# MCU.net
KiCad netlist of a schematic drawn in Altium Designer
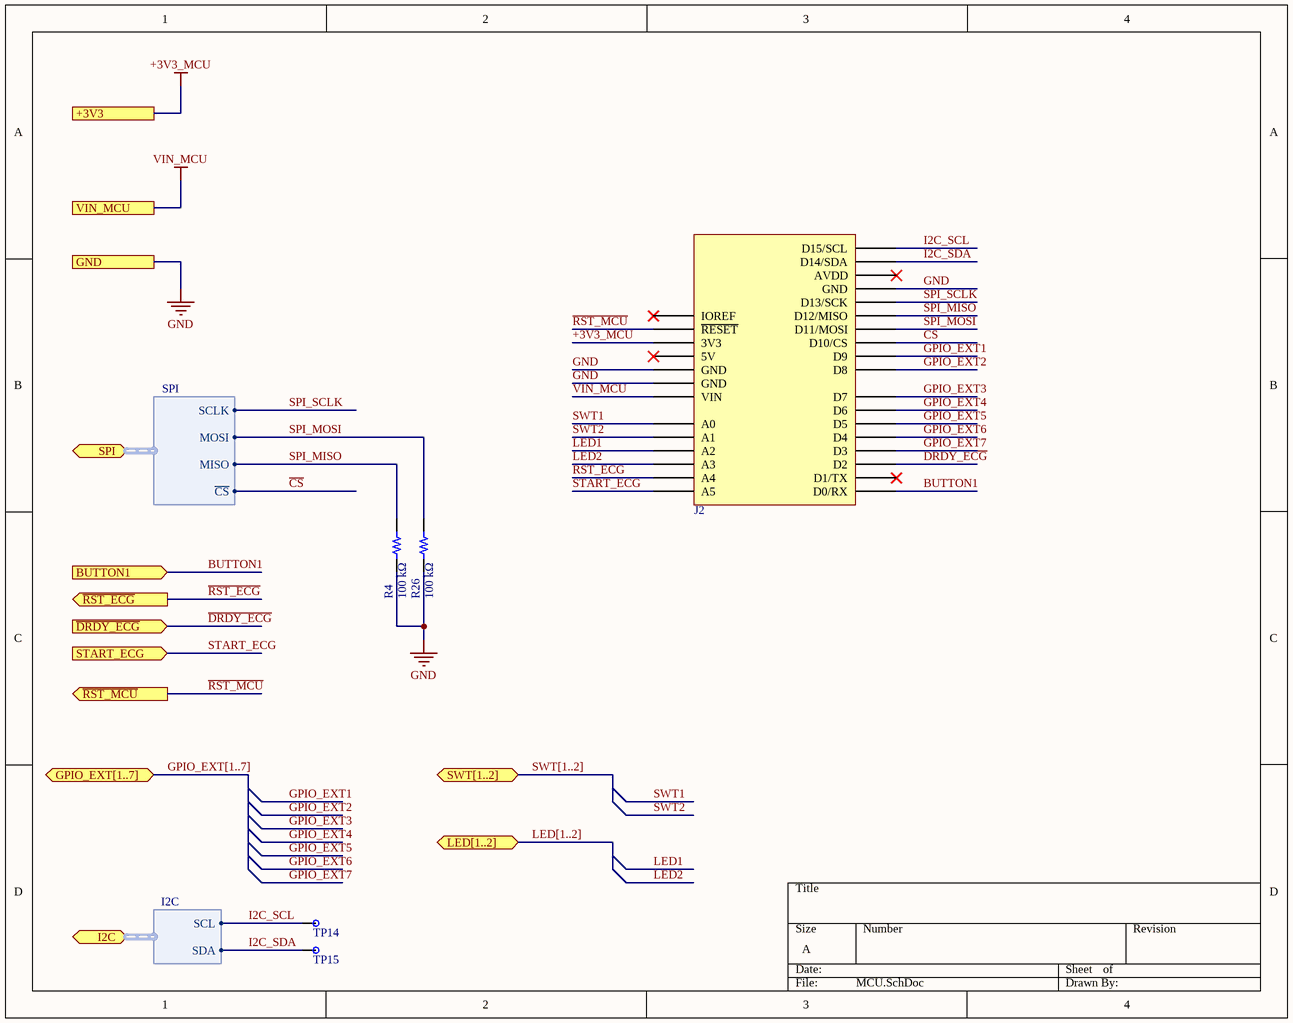
[diagram p0: MCU.SchDoc]

(export (version "E")
  (design (tool "Eeschema 10.0.6"))
  (components
    (comp (ref "J2")
      (value "920-0088-01")
      (footprint "SCHMARTBOARD - 920-0088-01")
      (description "CONN HDR 8/10P 0.1 GOLD PCB 6PC")
      (fields (field (name "MANUFACTURER") "Schmartboard, Inc."))
      (libsource (lib "Generic Altium Database") (part "Arduino Headers"))
    )
    (comp (ref "R4")
      (value "100 kΩ")
      (footprint "RES 0402_1005")
      (description "RES SMD 100K OHM 1% 1/16W 0402")
      (fields (field (name "PART NUMBER") "AC0402FR-07100KL") (field (name "MANUFACTURER") "Yageo"))
      (libsource (lib "Generic Altium Database") (part "Resistor"))
    )
    (comp (ref "R26")
      (value "100 kΩ")
      (footprint "RES 0402_1005")
      (description "RES SMD 100K OHM 1% 1/16W 0402")
      (fields (field (name "PART NUMBER") "AC0402FR-07100KL") (field (name "MANUFACTURER") "Yageo"))
      (libsource (lib "Generic Altium Database") (part "Resistor"))
    )
    (comp (ref "TP14")
      (value "TP1MM")
      (footprint "Test Point 1MM")
      (description "1MM Circular Test Point")
      (libsource (lib "Generic Altium Database") (part "Test Point"))
    )
    (comp (ref "TP15")
      (value "TP1MM")
      (footprint "Test Point 1MM")
      (description "1MM Circular Test Point")
      (libsource (lib "Generic Altium Database") (part "Test Point"))
    )
  )
  (nets
    (net (code "3") (name "+3V3_MCU") (class "Default")
      (node (ref "J2") (pin "4") (pinfunction "3V3_4") (pintype "passive"))
    )
    (net (code "4") (name "/BUTTON1") (class "Default")
      (node (ref "J2") (pin "15") (pinfunction "D0/RX_15") (pintype "passive"))
    )
    (net (code "5") (name "/GPIO_EXT1") (class "Default")
      (node (ref "J2") (pin "24") (pinfunction "D9_24") (pintype "passive"))
    )
    (net (code "6") (name "/GPIO_EXT2") (class "Default")
      (node (ref "J2") (pin "23") (pinfunction "D8_23") (pintype "passive"))
    )
    (net (code "7") (name "/GPIO_EXT3") (class "Default")
      (node (ref "J2") (pin "22") (pinfunction "D7_22") (pintype "passive"))
    )
    (net (code "8") (name "/GPIO_EXT4") (class "Default")
      (node (ref "J2") (pin "21") (pinfunction "D6_21") (pintype "passive"))
    )
    (net (code "9") (name "/GPIO_EXT5") (class "Default")
      (node (ref "J2") (pin "20") (pinfunction "D5_20") (pintype "passive"))
    )
    (net (code "10") (name "/GPIO_EXT6") (class "Default")
      (node (ref "J2") (pin "19") (pinfunction "D4_19") (pintype "passive"))
    )
    (net (code "11") (name "/GPIO_EXT7") (class "Default")
      (node (ref "J2") (pin "18") (pinfunction "D3_18") (pintype "passive"))
    )
    (net (code "13") (name "/I2C_SCL") (class "Default")
      (node (ref "J2") (pin "32") (pinfunction "D15/SCL_32") (pintype "passive"))
      (node (ref "TP14") (pin "1") (pintype "power_in"))
    )
    (net (code "14") (name "/I2C_SDA") (class "Default")
      (node (ref "J2") (pin "31") (pinfunction "D14/SDA_31") (pintype "passive"))
      (node (ref "TP15") (pin "1") (pintype "power_in"))
    )
    (net (code "15") (name "/LED1") (class "Default")
      (node (ref "J2") (pin "11") (pinfunction "A2_11") (pintype "passive"))
    )
    (net (code "16") (name "/LED2") (class "Default")
      (node (ref "J2") (pin "12") (pinfunction "A3_12") (pintype "passive"))
    )
    (net (code "18") (name "/SPI_MISO") (class "Default")
      (node (ref "J2") (pin "27") (pinfunction "D12/MISO_27") (pintype "passive"))
      (node (ref "R4") (pin "1") (pinfunction "1_1") (pintype "passive"))
    )
    (net (code "19") (name "/SPI_MOSI") (class "Default")
      (node (ref "J2") (pin "26") (pinfunction "D11/MOSI_26") (pintype "passive"))
      (node (ref "R26") (pin "1") (pinfunction "1_1") (pintype "passive"))
    )
    (net (code "20") (name "/SPI_SCLK") (class "Default")
      (node (ref "J2") (pin "28") (pinfunction "D13/SCK_28") (pintype "passive"))
    )
    (net (code "21") (name "/START_ECG") (class "Default")
      (node (ref "J2") (pin "14") (pinfunction "A5_14") (pintype "passive"))
    )
    (net (code "22") (name "/SWT1") (class "Default")
      (node (ref "J2") (pin "9") (pinfunction "A0_9") (pintype "passive"))
    )
    (net (code "23") (name "/SWT2") (class "Default")
      (node (ref "J2") (pin "10") (pinfunction "A1_10") (pintype "passive"))
    )
    (net (code "27") (name "/~{CS}") (class "Default")
      (node (ref "J2") (pin "25") (pinfunction "D10/CS_25") (pintype "passive"))
    )
    (net (code "28") (name "/~{DRDY_ECG}") (class "Default")
      (node (ref "J2") (pin "17") (pinfunction "D2_17") (pintype "passive"))
    )
    (net (code "29") (name "/~{RST_ECG}") (class "Default")
      (node (ref "J2") (pin "13") (pinfunction "A4_13") (pintype "passive"))
    )
    (net (code "30") (name "/~{RST_MCU}") (class "Default")
      (node (ref "J2") (pin "3") (pinfunction "~{RESET}_3") (pintype "passive"))
    )
    (net (code "31") (name "GND") (class "Default")
      (node (ref "J2") (pin "29") (pinfunction "GND_29") (pintype "passive"))
      (node (ref "J2") (pin "6") (pinfunction "GND_6") (pintype "passive"))
      (node (ref "J2") (pin "7") (pinfunction "GND_7") (pintype "passive"))
      (node (ref "R26") (pin "2") (pinfunction "2_2") (pintype "passive"))
      (node (ref "R4") (pin "2") (pinfunction "2_2") (pintype "passive"))
    )
    (net (code "32") (name "VIN_MCU") (class "Default")
      (node (ref "J2") (pin "8") (pinfunction "VIN_8") (pintype "passive"))
    )
    (net (code "33") (name "unconnected-(J2-5V-Pad5)") (class "Default")
      (node (ref "J2") (pin "5") (pinfunction "5V_5") (pintype "passive+no_connect"))
    )
    (net (code "34") (name "unconnected-(J2-AVDD-Pad30)") (class "Default")
      (node (ref "J2") (pin "30") (pinfunction "AVDD_30") (pintype "passive+no_connect"))
    )
    (net (code "35") (name "unconnected-(J2-D1{slash}TX-Pad16)") (class "Default")
      (node (ref "J2") (pin "16") (pinfunction "D1/TX_16") (pintype "passive+no_connect"))
    )
    (net (code "36") (name "unconnected-(J2-IOREF-Pad2)") (class "Default")
      (node (ref "J2") (pin "2") (pinfunction "IOREF_2") (pintype "passive+no_connect"))
    )
  )
)
